# pimp.net
KiCad netlist of a schematic drawn in EAGLE
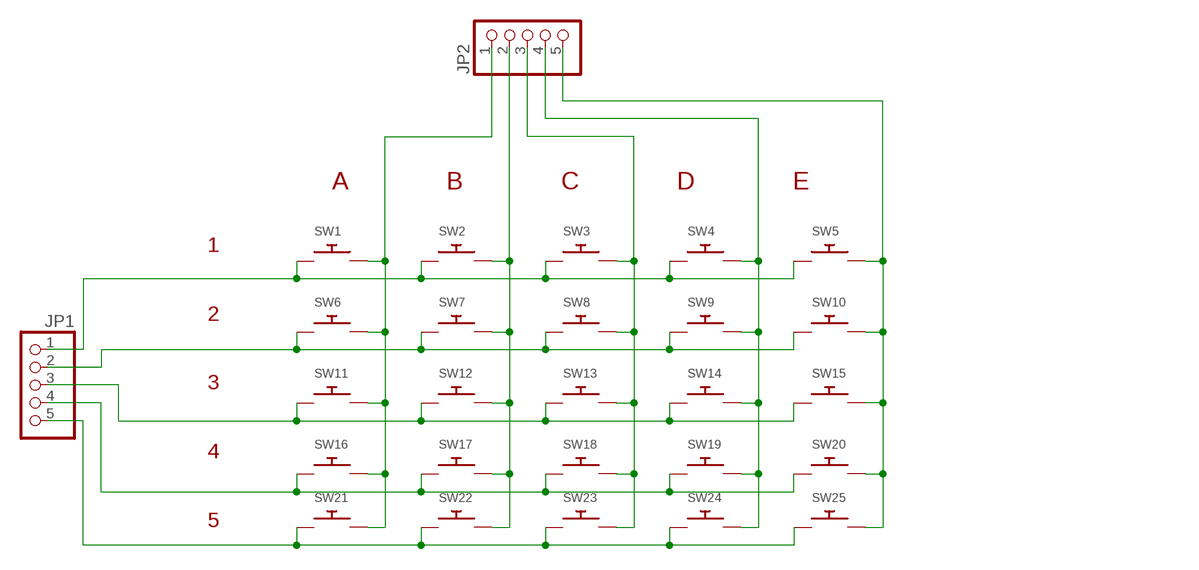
[diagram p0: schematic, sheet 1]

(export (version "E")
  (design (tool "Eeschema 10.0.6"))
  (components
    (comp (ref "JP1")
      (value "PINHD-1X5")
      (footprint "eagle-import:1X05")
      (libsource (lib "eagle-import") (part "PINHD-1X5"))
    )
    (comp (ref "JP2")
      (value "PINHD-1X5")
      (footprint "eagle-import:1X05")
      (libsource (lib "eagle-import") (part "PINHD-1X5"))
    )
    (comp (ref "SW1")
      (value "SWITCH_PUSHBUTTONC&K_KSS")
      (footprint "eagle-import:BTN_CK_KSS")
      (libsource (lib "eagle-import") (part "SWITCH_PUSHBUTTONC&K_KSS"))
    )
    (comp (ref "SW2")
      (value "SWITCH_PUSHBUTTONC&K_KSS")
      (footprint "eagle-import:BTN_CK_KSS")
      (libsource (lib "eagle-import") (part "SWITCH_PUSHBUTTONC&K_KSS"))
    )
    (comp (ref "SW3")
      (value "SWITCH_PUSHBUTTONC&K_KSS")
      (footprint "eagle-import:BTN_CK_KSS")
      (libsource (lib "eagle-import") (part "SWITCH_PUSHBUTTONC&K_KSS"))
    )
    (comp (ref "SW4")
      (value "SWITCH_PUSHBUTTONC&K_KSS")
      (footprint "eagle-import:BTN_CK_KSS")
      (libsource (lib "eagle-import") (part "SWITCH_PUSHBUTTONC&K_KSS"))
    )
    (comp (ref "SW5")
      (value "SWITCH_PUSHBUTTONC&K_KSS")
      (footprint "eagle-import:BTN_CK_KSS")
      (libsource (lib "eagle-import") (part "SWITCH_PUSHBUTTONC&K_KSS"))
    )
    (comp (ref "SW6")
      (value "SWITCH_PUSHBUTTONC&K_KSS")
      (footprint "eagle-import:BTN_CK_KSS")
      (libsource (lib "eagle-import") (part "SWITCH_PUSHBUTTONC&K_KSS"))
    )
    (comp (ref "SW7")
      (value "SWITCH_PUSHBUTTONC&K_KSS")
      (footprint "eagle-import:BTN_CK_KSS")
      (libsource (lib "eagle-import") (part "SWITCH_PUSHBUTTONC&K_KSS"))
    )
    (comp (ref "SW8")
      (value "SWITCH_PUSHBUTTONC&K_KSS")
      (footprint "eagle-import:BTN_CK_KSS")
      (libsource (lib "eagle-import") (part "SWITCH_PUSHBUTTONC&K_KSS"))
    )
    (comp (ref "SW9")
      (value "SWITCH_PUSHBUTTONC&K_KSS")
      (footprint "eagle-import:BTN_CK_KSS")
      (libsource (lib "eagle-import") (part "SWITCH_PUSHBUTTONC&K_KSS"))
    )
    (comp (ref "SW10")
      (value "SWITCH_PUSHBUTTONC&K_KSS")
      (footprint "eagle-import:BTN_CK_KSS")
      (libsource (lib "eagle-import") (part "SWITCH_PUSHBUTTONC&K_KSS"))
    )
    (comp (ref "SW11")
      (value "SWITCH_PUSHBUTTONC&K_KSS")
      (footprint "eagle-import:BTN_CK_KSS")
      (libsource (lib "eagle-import") (part "SWITCH_PUSHBUTTONC&K_KSS"))
    )
    (comp (ref "SW12")
      (value "SWITCH_PUSHBUTTONC&K_KSS")
      (footprint "eagle-import:BTN_CK_KSS")
      (libsource (lib "eagle-import") (part "SWITCH_PUSHBUTTONC&K_KSS"))
    )
    (comp (ref "SW13")
      (value "SWITCH_PUSHBUTTONC&K_KSS")
      (footprint "eagle-import:BTN_CK_KSS")
      (libsource (lib "eagle-import") (part "SWITCH_PUSHBUTTONC&K_KSS"))
    )
    (comp (ref "SW14")
      (value "SWITCH_PUSHBUTTONC&K_KSS")
      (footprint "eagle-import:BTN_CK_KSS")
      (libsource (lib "eagle-import") (part "SWITCH_PUSHBUTTONC&K_KSS"))
    )
    (comp (ref "SW15")
      (value "SWITCH_PUSHBUTTONC&K_KSS")
      (footprint "eagle-import:BTN_CK_KSS")
      (libsource (lib "eagle-import") (part "SWITCH_PUSHBUTTONC&K_KSS"))
    )
    (comp (ref "SW16")
      (value "SWITCH_PUSHBUTTONC&K_KSS")
      (footprint "eagle-import:BTN_CK_KSS")
      (libsource (lib "eagle-import") (part "SWITCH_PUSHBUTTONC&K_KSS"))
    )
    (comp (ref "SW17")
      (value "SWITCH_PUSHBUTTONC&K_KSS")
      (footprint "eagle-import:BTN_CK_KSS")
      (libsource (lib "eagle-import") (part "SWITCH_PUSHBUTTONC&K_KSS"))
    )
    (comp (ref "SW18")
      (value "SWITCH_PUSHBUTTONC&K_KSS")
      (footprint "eagle-import:BTN_CK_KSS")
      (libsource (lib "eagle-import") (part "SWITCH_PUSHBUTTONC&K_KSS"))
    )
    (comp (ref "SW19")
      (value "SWITCH_PUSHBUTTONC&K_KSS")
      (footprint "eagle-import:BTN_CK_KSS")
      (libsource (lib "eagle-import") (part "SWITCH_PUSHBUTTONC&K_KSS"))
    )
    (comp (ref "SW20")
      (value "SWITCH_PUSHBUTTONC&K_KSS")
      (footprint "eagle-import:BTN_CK_KSS")
      (libsource (lib "eagle-import") (part "SWITCH_PUSHBUTTONC&K_KSS"))
    )
    (comp (ref "SW21")
      (value "SWITCH_PUSHBUTTONC&K_KSS")
      (footprint "eagle-import:BTN_CK_KSS")
      (libsource (lib "eagle-import") (part "SWITCH_PUSHBUTTONC&K_KSS"))
    )
    (comp (ref "SW22")
      (value "SWITCH_PUSHBUTTONC&K_KSS")
      (footprint "eagle-import:BTN_CK_KSS")
      (libsource (lib "eagle-import") (part "SWITCH_PUSHBUTTONC&K_KSS"))
    )
    (comp (ref "SW23")
      (value "SWITCH_PUSHBUTTONC&K_KSS")
      (footprint "eagle-import:BTN_CK_KSS")
      (libsource (lib "eagle-import") (part "SWITCH_PUSHBUTTONC&K_KSS"))
    )
    (comp (ref "SW24")
      (value "SWITCH_PUSHBUTTONC&K_KSS")
      (footprint "eagle-import:BTN_CK_KSS")
      (libsource (lib "eagle-import") (part "SWITCH_PUSHBUTTONC&K_KSS"))
    )
    (comp (ref "SW25")
      (value "SWITCH_PUSHBUTTONC&K_KSS")
      (footprint "eagle-import:BTN_CK_KSS")
      (libsource (lib "eagle-import") (part "SWITCH_PUSHBUTTONC&K_KSS"))
    )
  )
  (nets
    (net (code "1") (name "Net-(JP1-Pad1)") (class "Default")
      (node (ref "JP1") (pin "1") (pinfunction "1_1") (pintype "passive"))
      (node (ref "SW1") (pin "P$1") (pinfunction "P$1_P$1") (pintype "passive"))
      (node (ref "SW2") (pin "P$1") (pinfunction "P$1_P$1") (pintype "passive"))
      (node (ref "SW3") (pin "P$1") (pinfunction "P$1_P$1") (pintype "passive"))
      (node (ref "SW4") (pin "P$1") (pinfunction "P$1_P$1") (pintype "passive"))
      (node (ref "SW5") (pin "P$1") (pinfunction "P$1_P$1") (pintype "passive"))
    )
    (net (code "2") (name "Net-(JP1-Pad2)") (class "Default")
      (node (ref "JP1") (pin "2") (pinfunction "2_2") (pintype "passive"))
      (node (ref "SW10") (pin "P$1") (pinfunction "P$1_P$1") (pintype "passive"))
      (node (ref "SW6") (pin "P$1") (pinfunction "P$1_P$1") (pintype "passive"))
      (node (ref "SW7") (pin "P$1") (pinfunction "P$1_P$1") (pintype "passive"))
      (node (ref "SW8") (pin "P$1") (pinfunction "P$1_P$1") (pintype "passive"))
      (node (ref "SW9") (pin "P$1") (pinfunction "P$1_P$1") (pintype "passive"))
    )
    (net (code "3") (name "Net-(JP1-Pad3)") (class "Default")
      (node (ref "JP1") (pin "3") (pinfunction "3_3") (pintype "passive"))
      (node (ref "SW11") (pin "P$1") (pinfunction "P$1_P$1") (pintype "passive"))
      (node (ref "SW12") (pin "P$1") (pinfunction "P$1_P$1") (pintype "passive"))
      (node (ref "SW13") (pin "P$1") (pinfunction "P$1_P$1") (pintype "passive"))
      (node (ref "SW14") (pin "P$1") (pinfunction "P$1_P$1") (pintype "passive"))
      (node (ref "SW15") (pin "P$1") (pinfunction "P$1_P$1") (pintype "passive"))
    )
    (net (code "4") (name "Net-(JP1-Pad4)") (class "Default")
      (node (ref "JP1") (pin "4") (pinfunction "4_4") (pintype "passive"))
      (node (ref "SW16") (pin "P$1") (pinfunction "P$1_P$1") (pintype "passive"))
      (node (ref "SW17") (pin "P$1") (pinfunction "P$1_P$1") (pintype "passive"))
      (node (ref "SW18") (pin "P$1") (pinfunction "P$1_P$1") (pintype "passive"))
      (node (ref "SW19") (pin "P$1") (pinfunction "P$1_P$1") (pintype "passive"))
      (node (ref "SW20") (pin "P$1") (pinfunction "P$1_P$1") (pintype "passive"))
    )
    (net (code "5") (name "Net-(JP1-Pad5)") (class "Default")
      (node (ref "JP1") (pin "5") (pinfunction "5_5") (pintype "passive"))
      (node (ref "SW21") (pin "P$1") (pinfunction "P$1_P$1") (pintype "passive"))
      (node (ref "SW22") (pin "P$1") (pinfunction "P$1_P$1") (pintype "passive"))
      (node (ref "SW23") (pin "P$1") (pinfunction "P$1_P$1") (pintype "passive"))
      (node (ref "SW24") (pin "P$1") (pinfunction "P$1_P$1") (pintype "passive"))
      (node (ref "SW25") (pin "P$1") (pinfunction "P$1_P$1") (pintype "passive"))
    )
    (net (code "6") (name "Net-(JP2-Pad1)") (class "Default")
      (node (ref "JP2") (pin "1") (pinfunction "1_1") (pintype "passive"))
      (node (ref "SW1") (pin "P$2") (pinfunction "P$2_P$2") (pintype "passive"))
      (node (ref "SW11") (pin "P$2") (pinfunction "P$2_P$2") (pintype "passive"))
      (node (ref "SW16") (pin "P$2") (pinfunction "P$2_P$2") (pintype "passive"))
      (node (ref "SW21") (pin "P$2") (pinfunction "P$2_P$2") (pintype "passive"))
      (node (ref "SW6") (pin "P$2") (pinfunction "P$2_P$2") (pintype "passive"))
    )
    (net (code "7") (name "Net-(JP2-Pad2)") (class "Default")
      (node (ref "JP2") (pin "2") (pinfunction "2_2") (pintype "passive"))
      (node (ref "SW12") (pin "P$2") (pinfunction "P$2_P$2") (pintype "passive"))
      (node (ref "SW17") (pin "P$2") (pinfunction "P$2_P$2") (pintype "passive"))
      (node (ref "SW2") (pin "P$2") (pinfunction "P$2_P$2") (pintype "passive"))
      (node (ref "SW22") (pin "P$2") (pinfunction "P$2_P$2") (pintype "passive"))
      (node (ref "SW7") (pin "P$2") (pinfunction "P$2_P$2") (pintype "passive"))
    )
    (net (code "8") (name "Net-(JP2-Pad3)") (class "Default")
      (node (ref "JP2") (pin "3") (pinfunction "3_3") (pintype "passive"))
      (node (ref "SW13") (pin "P$2") (pinfunction "P$2_P$2") (pintype "passive"))
      (node (ref "SW18") (pin "P$2") (pinfunction "P$2_P$2") (pintype "passive"))
      (node (ref "SW23") (pin "P$2") (pinfunction "P$2_P$2") (pintype "passive"))
      (node (ref "SW3") (pin "P$2") (pinfunction "P$2_P$2") (pintype "passive"))
      (node (ref "SW8") (pin "P$2") (pinfunction "P$2_P$2") (pintype "passive"))
    )
    (net (code "9") (name "Net-(JP2-Pad4)") (class "Default")
      (node (ref "JP2") (pin "4") (pinfunction "4_4") (pintype "passive"))
      (node (ref "SW14") (pin "P$2") (pinfunction "P$2_P$2") (pintype "passive"))
      (node (ref "SW19") (pin "P$2") (pinfunction "P$2_P$2") (pintype "passive"))
      (node (ref "SW24") (pin "P$2") (pinfunction "P$2_P$2") (pintype "passive"))
      (node (ref "SW4") (pin "P$2") (pinfunction "P$2_P$2") (pintype "passive"))
      (node (ref "SW9") (pin "P$2") (pinfunction "P$2_P$2") (pintype "passive"))
    )
    (net (code "10") (name "Net-(JP2-Pad5)") (class "Default")
      (node (ref "JP2") (pin "5") (pinfunction "5_5") (pintype "passive"))
      (node (ref "SW10") (pin "P$2") (pinfunction "P$2_P$2") (pintype "passive"))
      (node (ref "SW15") (pin "P$2") (pinfunction "P$2_P$2") (pintype "passive"))
      (node (ref "SW20") (pin "P$2") (pinfunction "P$2_P$2") (pintype "passive"))
      (node (ref "SW25") (pin "P$2") (pinfunction "P$2_P$2") (pintype "passive"))
      (node (ref "SW5") (pin "P$2") (pinfunction "P$2_P$2") (pintype "passive"))
    )
  )
)
